# SCH_PCB_Build_2026-03-27.net
KiCad netlist of a schematic drawn in EasyEDA
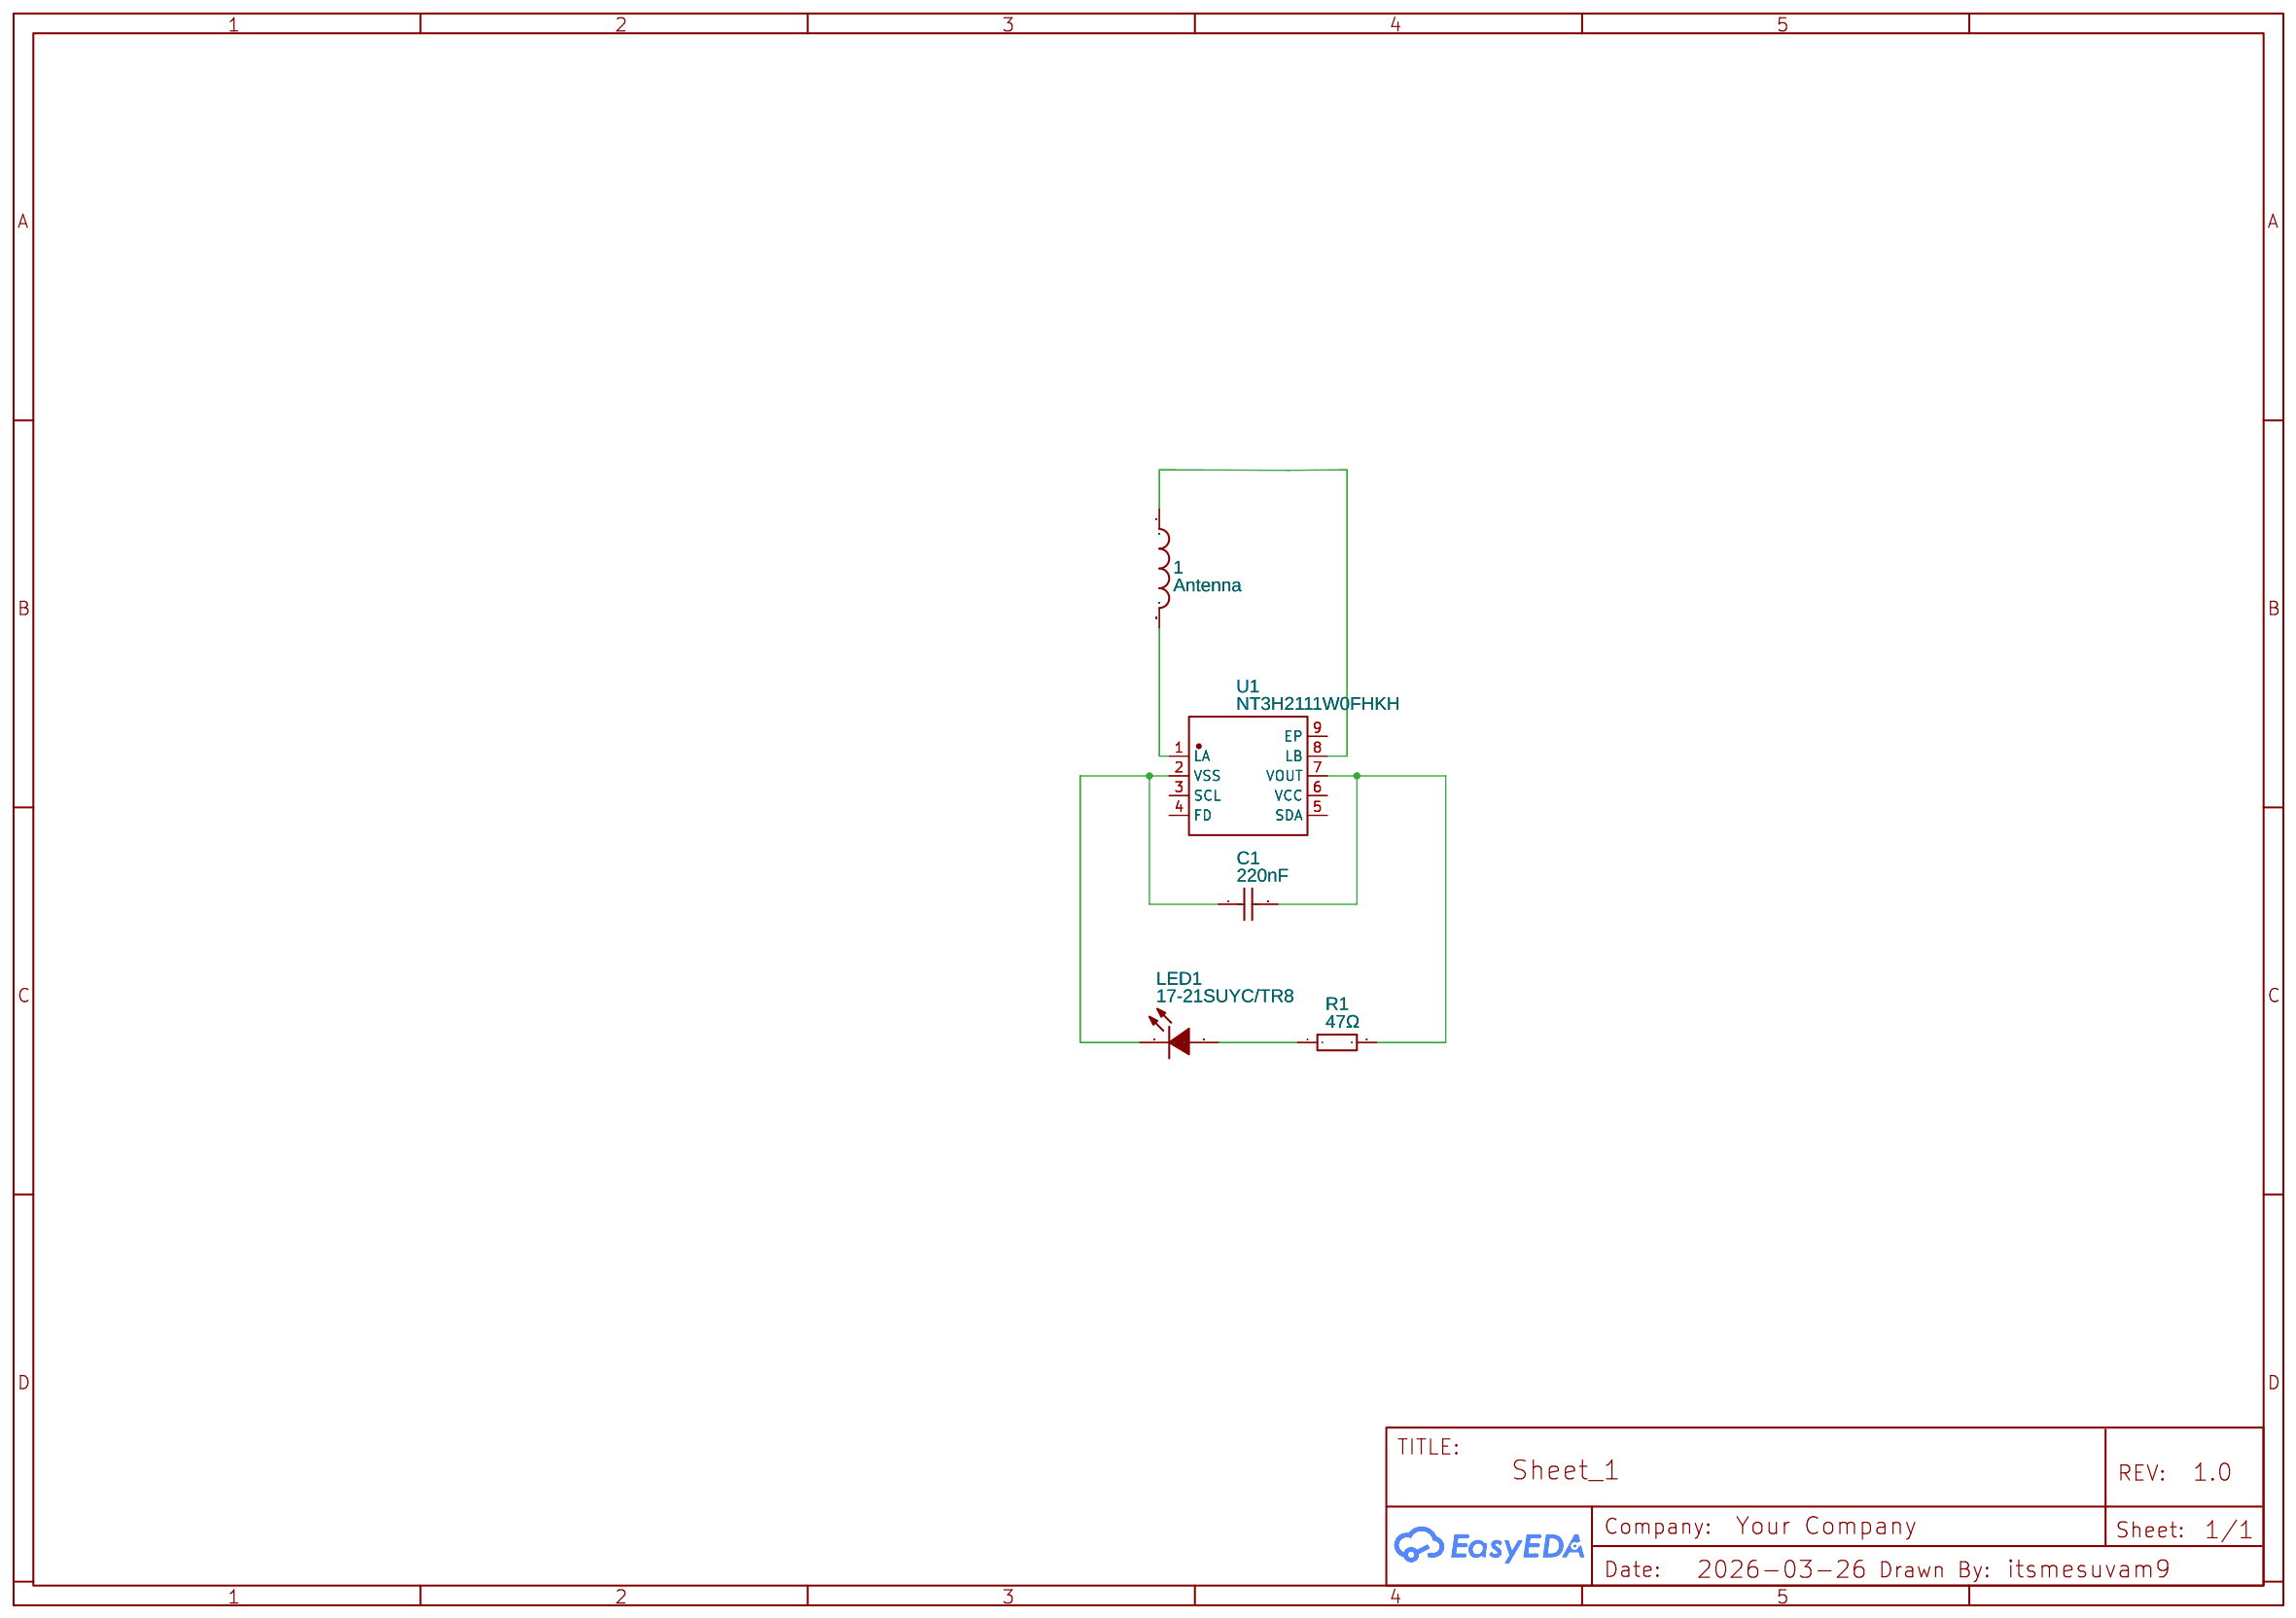
[diagram p0: schematic sheet]

(export (version "E")
  (design (tool "Eeschema 10.0.6"))
  (components
    (comp (ref "1") (value "Antenna") (libsource (lib "") (part "Antenna")))
    (comp (ref "C1")
      (value "220nF")
      (fields
        (field (name "Manufacturer Part") "CL10B224KA8NNNC")
        (field (name "Manufacturer") "SAMSUNG(三星)")
      )
      (libsource (lib "") (part "CL10B224KA8NNNC"))
    )
    (comp (ref "LED1")
      (value "17-21SUYC/TR8")
      (fields (field (name "Manufacturer Part") "KT-0805黄灯") (field (name "Manufacturer") "KENTO"))
      (libsource (lib "") (part "17-21SUYC/TR8"))
    )
    (comp (ref "R1")
      (value "47Ω")
      (fields
        (field (name "Manufacturer Part") "0603WAF470JT5E")
        (field (name "Manufacturer") "UNI-ROYAL(厚声)")
      )
      (libsource (lib "") (part "0603WAF470JT5E"))
    )
    (comp (ref "U1")
      (value "NT3H2111W0FHKH")
      (fields (field (name "Manufacturer") "NXP(恩智浦)"))
      (libsource (lib "") (part "NT3H2111W0FHKH"))
    )
  )
  (nets
    (net (code "1") (name "Net-(LED1-+)") (class "Default")
      (node (ref "LED1") (pin "1") (pinfunction "+_1") (pintype "unspecified"))
      (node (ref "R1") (pin "1") (pinfunction "1_1") (pintype "input"))
    )
    (net (code "2") (name "Net-(LED1--)") (class "Default")
      (node (ref "C1") (pin "1") (pinfunction "1_1") (pintype "input"))
      (node (ref "LED1") (pin "2") (pinfunction "-_2") (pintype "unspecified"))
      (node (ref "U1") (pin "2") (pinfunction "VSS_2") (pintype "unspecified"))
    )
    (net (code "3") (name "Net-(U1-LA)") (class "Default")
      (node (ref "1") (pin "P$1") (pinfunction "P$1_P$1") (pintype "unspecified"))
      (node (ref "U1") (pin "1") (pinfunction "LA_1") (pintype "unspecified"))
    )
    (net (code "4") (name "Net-(U1-LB)") (class "Default")
      (node (ref "1") (pin "P$2") (pinfunction "P$2_P$2") (pintype "unspecified"))
      (node (ref "U1") (pin "8") (pinfunction "LB_8") (pintype "unspecified"))
    )
    (net (code "5") (name "Net-(U1-VOUT)") (class "Default")
      (node (ref "C1") (pin "2") (pinfunction "2_2") (pintype "input"))
      (node (ref "R1") (pin "2") (pinfunction "2_2") (pintype "input"))
      (node (ref "U1") (pin "7") (pinfunction "VOUT_7") (pintype "unspecified"))
    )
    (net (code "6") (name "unconnected-(U1-EP-Pad9)") (class "Default")
      (node (ref "U1") (pin "9") (pinfunction "EP_9") (pintype "unspecified"))
    )
    (net (code "7") (name "unconnected-(U1-FD-Pad4)") (class "Default")
      (node (ref "U1") (pin "4") (pinfunction "FD_4") (pintype "unspecified"))
    )
    (net (code "8") (name "unconnected-(U1-SCL-Pad3)") (class "Default")
      (node (ref "U1") (pin "3") (pinfunction "SCL_3") (pintype "unspecified"))
    )
    (net (code "9") (name "unconnected-(U1-SDA-Pad5)") (class "Default")
      (node (ref "U1") (pin "5") (pinfunction "SDA_5") (pintype "unspecified"))
    )
    (net (code "10") (name "unconnected-(U1-VCC-Pad6)") (class "Default")
      (node (ref "U1") (pin "6") (pinfunction "VCC_6") (pintype "unspecified"))
    )
  )
)
